# Final_Project.net
KiCad netlist of a schematic drawn in EAGLE
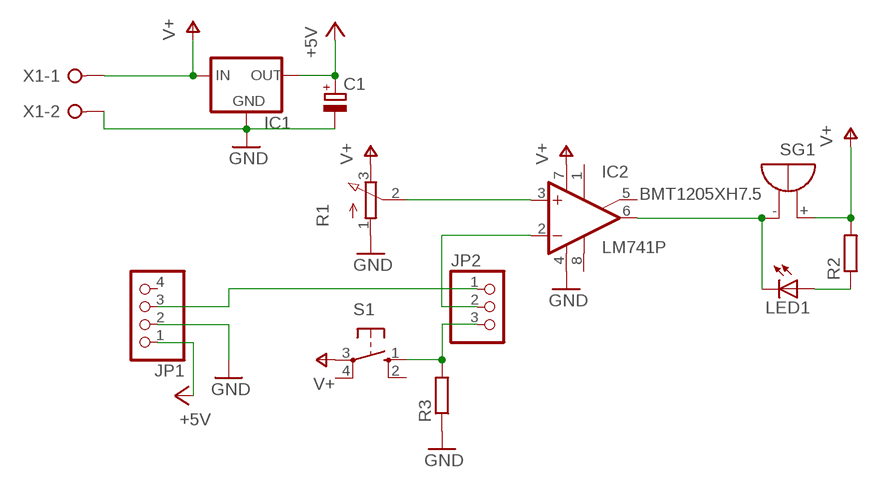
[diagram p0: schematic, sheet 1]

(export (version "E")
  (design (tool "Eeschema 10.0.6"))
  (components
    (comp (ref "C1")
      (value "CPOL-EUE2.5-7")
      (footprint "eagle-import:E2,5-7")
      (libsource (lib "eagle-import") (part "CPOL-EUE2.5-7"))
    )
    (comp (ref "IC1")
      (value "78MXXS")
      (footprint "eagle-import:78MXXS")
      (libsource (lib "eagle-import") (part "78MXXS"))
    )
    (comp (ref "IC2")
      (value "LM741P")
      (footprint "eagle-import:DIL08")
      (libsource (lib "eagle-import") (part "741PLM"))
    )
    (comp (ref "JP1")
      (value "PINHD-1X4")
      (footprint "eagle-import:1X04")
      (libsource (lib "eagle-import") (part "PINHD-1X4"))
    )
    (comp (ref "JP2")
      (value "PINHD-1X3")
      (footprint "eagle-import:1X03")
      (libsource (lib "eagle-import") (part "PINHD-1X3"))
    )
    (comp (ref "LED1")
      (value "LED5MM")
      (footprint "eagle-import:LED5MM")
      (libsource (lib "eagle-import") (part "LED5MM"))
    )
    (comp (ref "R1")
      (value "3RP/1610N")
      (footprint "eagle-import:3RP_1610N")
      (libsource (lib "eagle-import") (part "3RP/1610N"))
    )
    (comp (ref "R2")
      (value "R-EU_0207/7")
      (footprint "eagle-import:0207_7")
      (libsource (lib "eagle-import") (part "R-EU_0207/7"))
    )
    (comp (ref "R3")
      (value "R-EU_0207/7")
      (footprint "eagle-import:0207_7")
      (libsource (lib "eagle-import") (part "R-EU_0207/7"))
    )
    (comp (ref "S1")
      (value "10-XX")
      (footprint "eagle-import:B3F-10XX")
      (fields (field (name "MPN") "B3F-1000"))
      (libsource (lib "eagle-import") (part "10-XX"))
    )
    (comp (ref "SG1")
      (value "BMT1205XH7.5")
      (footprint "eagle-import:BMT1205XH7.5")
      (libsource (lib "eagle-import") (part "BMT1205XH7.5"))
    )
    (comp (ref "X1")
      (value "W237-02P")
      (footprint "eagle-import:W237-132")
      (libsource (lib "eagle-import") (part "W237-02P"))
    )
  )
  (nets
    (net (code "1") (name "+5V") (class "Default")
      (node (ref "C1") (pin "+") (pinfunction "+_+") (pintype "passive"))
      (node (ref "IC1") (pin "OUT") (pinfunction "OUT_OUT") (pintype "passive"))
      (node (ref "JP1") (pin "1") (pinfunction "1_1") (pintype "passive"))
    )
    (net (code "2") (name "GND") (class "Default")
      (node (ref "C1") (pin "-") (pinfunction "-_-") (pintype "passive"))
      (node (ref "IC1") (pin "GND") (pinfunction "GND_GND") (pintype "input"))
      (node (ref "IC2") (pin "4") (pinfunction "V-_4") (pintype "power_in"))
      (node (ref "JP1") (pin "2") (pinfunction "2_2") (pintype "passive"))
      (node (ref "R1") (pin "1") (pinfunction "A_1") (pintype "passive"))
      (node (ref "R3") (pin "1") (pinfunction "1_1") (pintype "passive"))
      (node (ref "X1") (pin "2") (pinfunction "KL_2") (pintype "passive"))
    )
    (net (code "3") (name "Net-(IC2-+IN)") (class "Default")
      (node (ref "IC2") (pin "3") (pinfunction "+IN_3") (pintype "input"))
      (node (ref "R1") (pin "2") (pinfunction "S_2") (pintype "passive"))
    )
    (net (code "4") (name "Net-(IC2--IN)") (class "Default")
      (node (ref "IC2") (pin "2") (pinfunction "-IN_2") (pintype "input"))
      (node (ref "JP2") (pin "2") (pinfunction "2_2") (pintype "passive"))
    )
    (net (code "5") (name "Net-(IC2-OUT)") (class "Default")
      (node (ref "IC2") (pin "6") (pinfunction "OUT_6") (pintype "output"))
      (node (ref "LED1") (pin "K") (pinfunction "C_K") (pintype "passive"))
      (node (ref "SG1") (pin "-") (pinfunction "-_-") (pintype "passive"))
    )
    (net (code "6") (name "Net-(JP1-Pad3)") (class "Default")
      (node (ref "JP1") (pin "3") (pinfunction "3_3") (pintype "passive"))
      (node (ref "JP2") (pin "1") (pinfunction "1_1") (pintype "passive"))
    )
    (net (code "7") (name "Net-(LED1-PadA)") (class "Default")
      (node (ref "LED1") (pin "A") (pinfunction "A_A") (pintype "passive"))
      (node (ref "R2") (pin "1") (pinfunction "1_1") (pintype "passive"))
    )
    (net (code "8") (name "Net-(S1-S)") (class "Default")
      (node (ref "JP2") (pin "3") (pinfunction "3_3") (pintype "passive"))
      (node (ref "R3") (pin "2") (pinfunction "2_2") (pintype "passive"))
      (node (ref "S1") (pin "1") (pinfunction "S_1") (pintype "passive"))
    )
    (net (code "9") (name "V+") (class "Default")
      (node (ref "IC1") (pin "IN") (pinfunction "IN_IN") (pintype "input"))
      (node (ref "IC2") (pin "7") (pinfunction "V+_7") (pintype "power_in"))
      (node (ref "R1") (pin "3") (pinfunction "E_3") (pintype "passive"))
      (node (ref "R2") (pin "2") (pinfunction "2_2") (pintype "passive"))
      (node (ref "S1") (pin "3") (pinfunction "P_3") (pintype "passive"))
      (node (ref "SG1") (pin "+") (pinfunction "+_+") (pintype "passive"))
      (node (ref "X1") (pin "1") (pinfunction "KL_1") (pintype "passive"))
    )
    (net (code "10") (name "unconnected-(IC2-ON1-Pad1)") (class "Default")
      (node (ref "IC2") (pin "1") (pinfunction "ON1_1") (pintype "passive"))
    )
    (net (code "11") (name "unconnected-(IC2-ON2-Pad5)") (class "Default")
      (node (ref "IC2") (pin "5") (pinfunction "ON2_5") (pintype "passive"))
    )
    (net (code "12") (name "unconnected-(IC2-OPT-Pad8)") (class "Default")
      (node (ref "IC2") (pin "8") (pinfunction "OPT_8") (pintype "passive"))
    )
    (net (code "13") (name "unconnected-(JP1-Pad4)") (class "Default")
      (node (ref "JP1") (pin "4") (pinfunction "4_4") (pintype "passive"))
    )
    (net (code "14") (name "unconnected-(S1-P1-Pad4)") (class "Default")
      (node (ref "S1") (pin "4") (pinfunction "P1_4") (pintype "passive"))
    )
    (net (code "15") (name "unconnected-(S1-S1-Pad2)") (class "Default")
      (node (ref "S1") (pin "2") (pinfunction "S1_2") (pintype "passive"))
    )
  )
)
